# EEG_Inputs.net
KiCad netlist of a schematic drawn in Altium Designer
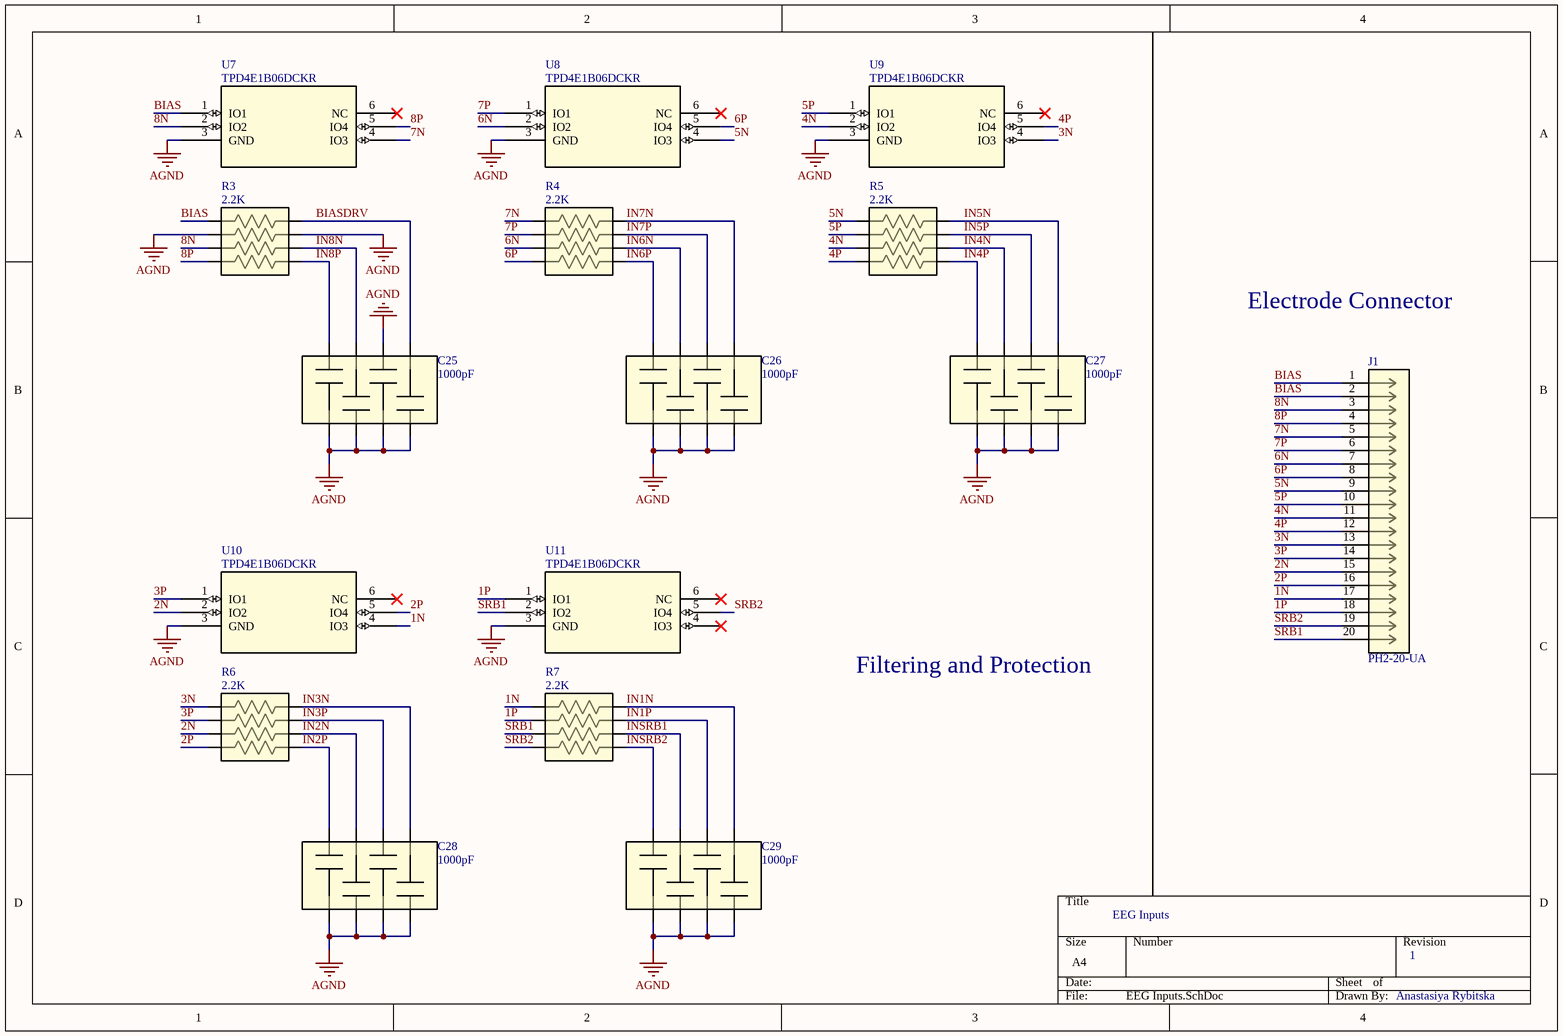
[diagram p0: EEG Inputs.SchDoc]

(export (version "E")
  (design (tool "Eeschema 10.0.6"))
  (components
    (comp (ref "C25")
      (value "CA0612KRX7R9BB102")
      (footprint "CAP_CA0612_3P2X1P6_YAG")
      (fields (field (name "CAPACITANCE") "1000pF"))
      (libsource (lib "Schlib1") (part "CA0612KRX7R9BB102"))
    )
    (comp (ref "C26")
      (value "CA0612KRX7R9BB102")
      (footprint "CAP_CA0612_3P2X1P6_YAG")
      (fields (field (name "CAPACITANCE") "1000pF"))
      (libsource (lib "Schlib1") (part "CA0612KRX7R9BB102"))
    )
    (comp (ref "C27")
      (value "CA0612KRX7R9BB102")
      (footprint "CAP_CA0612_3P2X1P6_YAG")
      (fields (field (name "CAPACITANCE") "1000pF"))
      (libsource (lib "Schlib1") (part "CA0612KRX7R9BB102"))
    )
    (comp (ref "C28")
      (value "CA0612KRX7R9BB102")
      (footprint "CAP_CA0612_3P2X1P6_YAG")
      (fields (field (name "CAPACITANCE") "1000pF"))
      (libsource (lib "Schlib1") (part "CA0612KRX7R9BB102"))
    )
    (comp (ref "C29")
      (value "CA0612KRX7R9BB102")
      (footprint "CAP_CA0612_3P2X1P6_YAG")
      (fields (field (name "CAPACITANCE") "1000pF"))
      (libsource (lib "Schlib1") (part "CA0612KRX7R9BB102"))
    )
    (comp (ref "J1")
      (value "PH2-20-UA")
      (footprint "CONN_PH2-20-UA_ADM")
      (description "No Description Available")
      (fields (field (name "COPYRIGHT") "Copyright (C) 2024 Ultra Librarian. All rights reserved."))
      (libsource (lib "Schlib1") (part "PH2-20-UA"))
    )
    (comp (ref "R3")
      (value "CAY16-2201F4LF")
      (footprint "CAY16_BRN")
      (description "No Description Available")
      (fields
        (field (name "RESISTANCE") "2.2K")
        (field (name "COPYRIGHT") "Copyright (C) 2023 Ultra Librarian. All rights reserved.")
      )
      (libsource (lib "Schlib1") (part "CAY16-2201F4LF"))
    )
    (comp (ref "R4")
      (value "CAY16-2201F4LF")
      (footprint "CAY16_BRN")
      (description "No Description Available")
      (fields
        (field (name "RESISTANCE") "2.2K")
        (field (name "COPYRIGHT") "Copyright (C) 2023 Ultra Librarian. All rights reserved.")
      )
      (libsource (lib "Schlib1") (part "CAY16-2201F4LF"))
    )
    (comp (ref "R5")
      (value "CAY16-2201F4LF")
      (footprint "CAY16_BRN")
      (description "No Description Available")
      (fields
        (field (name "RESISTANCE") "2.2K")
        (field (name "COPYRIGHT") "Copyright (C) 2023 Ultra Librarian. All rights reserved.")
      )
      (libsource (lib "Schlib1") (part "CAY16-2201F4LF"))
    )
    (comp (ref "R6")
      (value "CAY16-2201F4LF")
      (footprint "CAY16_BRN")
      (description "No Description Available")
      (fields
        (field (name "RESISTANCE") "2.2K")
        (field (name "COPYRIGHT") "Copyright (C) 2023 Ultra Librarian. All rights reserved.")
      )
      (libsource (lib "Schlib1") (part "CAY16-2201F4LF"))
    )
    (comp (ref "R7")
      (value "CAY16-2201F4LF")
      (footprint "CAY16_BRN")
      (description "No Description Available")
      (fields
        (field (name "RESISTANCE") "2.2K")
        (field (name "COPYRIGHT") "Copyright (C) 2023 Ultra Librarian. All rights reserved.")
      )
      (libsource (lib "Schlib1") (part "CAY16-2201F4LF"))
    )
    (comp (ref "U7")
      (value "TPD4E1B06DCKR")
      (footprint "DCK6_TEX")
      (description "No Description Available")
      (fields (field (name "COPYRIGHT") "Copyright (C) 2023 Ultra Librarian. All rights reserved."))
      (libsource (lib "Schlib1") (part "TPD4E1B06DCKR"))
    )
    (comp (ref "U8")
      (value "TPD4E1B06DCKR")
      (footprint "DCK6_TEX")
      (description "No Description Available")
      (fields (field (name "COPYRIGHT") "Copyright (C) 2023 Ultra Librarian. All rights reserved."))
      (libsource (lib "Schlib1") (part "TPD4E1B06DCKR"))
    )
    (comp (ref "U9")
      (value "TPD4E1B06DCKR")
      (footprint "DCK6_TEX")
      (description "No Description Available")
      (fields (field (name "COPYRIGHT") "Copyright (C) 2023 Ultra Librarian. All rights reserved."))
      (libsource (lib "Schlib1") (part "TPD4E1B06DCKR"))
    )
    (comp (ref "U10")
      (value "TPD4E1B06DCKR")
      (footprint "DCK6_TEX")
      (description "No Description Available")
      (fields (field (name "COPYRIGHT") "Copyright (C) 2023 Ultra Librarian. All rights reserved."))
      (libsource (lib "Schlib1") (part "TPD4E1B06DCKR"))
    )
    (comp (ref "U11")
      (value "TPD4E1B06DCKR")
      (footprint "DCK6_TEX")
      (description "No Description Available")
      (fields (field (name "COPYRIGHT") "Copyright (C) 2023 Ultra Librarian. All rights reserved."))
      (libsource (lib "Schlib1") (part "TPD4E1B06DCKR"))
    )
  )
  (nets
    (net (code "1") (name "/1N") (class "Default")
      (node (ref "J1") (pin "17") (pinfunction "17_17") (pintype "passive"))
      (node (ref "R7") (pin "1") (pinfunction "1_1") (pintype "passive"))
      (node (ref "U10") (pin "4") (pinfunction "IO3_4") (pintype "bidirectional"))
    )
    (net (code "2") (name "/1P") (class "Default")
      (node (ref "J1") (pin "18") (pinfunction "18_18") (pintype "passive"))
      (node (ref "R7") (pin "2") (pinfunction "2_2") (pintype "passive"))
      (node (ref "U11") (pin "1") (pinfunction "IO1_1") (pintype "bidirectional"))
    )
    (net (code "3") (name "/2N") (class "Default")
      (node (ref "J1") (pin "15") (pinfunction "15_15") (pintype "passive"))
      (node (ref "R6") (pin "3") (pinfunction "3_3") (pintype "passive"))
      (node (ref "U10") (pin "2") (pinfunction "IO2_2") (pintype "bidirectional"))
    )
    (net (code "4") (name "/2P") (class "Default")
      (node (ref "J1") (pin "16") (pinfunction "16_16") (pintype "passive"))
      (node (ref "R6") (pin "4") (pinfunction "4_4") (pintype "passive"))
      (node (ref "U10") (pin "5") (pinfunction "IO4_5") (pintype "bidirectional"))
    )
    (net (code "5") (name "/3N") (class "Default")
      (node (ref "J1") (pin "13") (pinfunction "13_13") (pintype "passive"))
      (node (ref "R6") (pin "1") (pinfunction "1_1") (pintype "passive"))
      (node (ref "U9") (pin "4") (pinfunction "IO3_4") (pintype "bidirectional"))
    )
    (net (code "6") (name "/3P") (class "Default")
      (node (ref "J1") (pin "14") (pinfunction "14_14") (pintype "passive"))
      (node (ref "R6") (pin "2") (pinfunction "2_2") (pintype "passive"))
      (node (ref "U10") (pin "1") (pinfunction "IO1_1") (pintype "bidirectional"))
    )
    (net (code "7") (name "/4N") (class "Default")
      (node (ref "J1") (pin "11") (pinfunction "11_11") (pintype "passive"))
      (node (ref "R5") (pin "3") (pinfunction "3_3") (pintype "passive"))
      (node (ref "U9") (pin "2") (pinfunction "IO2_2") (pintype "bidirectional"))
    )
    (net (code "8") (name "/4P") (class "Default")
      (node (ref "J1") (pin "12") (pinfunction "12_12") (pintype "passive"))
      (node (ref "R5") (pin "4") (pinfunction "4_4") (pintype "passive"))
      (node (ref "U9") (pin "5") (pinfunction "IO4_5") (pintype "bidirectional"))
    )
    (net (code "9") (name "/5N") (class "Default")
      (node (ref "J1") (pin "9") (pinfunction "9_9") (pintype "passive"))
      (node (ref "R5") (pin "1") (pinfunction "1_1") (pintype "passive"))
      (node (ref "U8") (pin "4") (pinfunction "IO3_4") (pintype "bidirectional"))
    )
    (net (code "10") (name "/5P") (class "Default")
      (node (ref "J1") (pin "10") (pinfunction "10_10") (pintype "passive"))
      (node (ref "R5") (pin "2") (pinfunction "2_2") (pintype "passive"))
      (node (ref "U9") (pin "1") (pinfunction "IO1_1") (pintype "bidirectional"))
    )
    (net (code "11") (name "/6N") (class "Default")
      (node (ref "J1") (pin "7") (pinfunction "7_7") (pintype "passive"))
      (node (ref "R4") (pin "3") (pinfunction "3_3") (pintype "passive"))
      (node (ref "U8") (pin "2") (pinfunction "IO2_2") (pintype "bidirectional"))
    )
    (net (code "12") (name "/6P") (class "Default")
      (node (ref "J1") (pin "8") (pinfunction "8_8") (pintype "passive"))
      (node (ref "R4") (pin "4") (pinfunction "4_4") (pintype "passive"))
      (node (ref "U8") (pin "5") (pinfunction "IO4_5") (pintype "bidirectional"))
    )
    (net (code "13") (name "/7N") (class "Default")
      (node (ref "J1") (pin "5") (pinfunction "5_5") (pintype "passive"))
      (node (ref "R4") (pin "1") (pinfunction "1_1") (pintype "passive"))
      (node (ref "U7") (pin "4") (pinfunction "IO3_4") (pintype "bidirectional"))
    )
    (net (code "14") (name "/7P") (class "Default")
      (node (ref "J1") (pin "6") (pinfunction "6_6") (pintype "passive"))
      (node (ref "R4") (pin "2") (pinfunction "2_2") (pintype "passive"))
      (node (ref "U8") (pin "1") (pinfunction "IO1_1") (pintype "bidirectional"))
    )
    (net (code "15") (name "/8N") (class "Default")
      (node (ref "J1") (pin "3") (pinfunction "3_3") (pintype "passive"))
      (node (ref "R3") (pin "3") (pinfunction "3_3") (pintype "passive"))
      (node (ref "U7") (pin "2") (pinfunction "IO2_2") (pintype "bidirectional"))
    )
    (net (code "16") (name "/8P") (class "Default")
      (node (ref "J1") (pin "4") (pinfunction "4_4") (pintype "passive"))
      (node (ref "R3") (pin "4") (pinfunction "4_4") (pintype "passive"))
      (node (ref "U7") (pin "5") (pinfunction "IO4_5") (pintype "bidirectional"))
    )
    (net (code "17") (name "/BIAS") (class "Default")
      (node (ref "J1") (pin "1") (pinfunction "1_1") (pintype "passive"))
      (node (ref "J1") (pin "2") (pinfunction "2_2") (pintype "passive"))
      (node (ref "R3") (pin "1") (pinfunction "1_1") (pintype "passive"))
      (node (ref "U7") (pin "1") (pinfunction "IO1_1") (pintype "bidirectional"))
    )
    (net (code "18") (name "/BIASDRV") (class "Default")
      (node (ref "C25") (pin "5") (pinfunction "5_5") (pintype "passive"))
      (node (ref "R3") (pin "8") (pinfunction "8_8") (pintype "passive"))
    )
    (net (code "19") (name "/IN1N") (class "Default")
      (node (ref "C29") (pin "5") (pinfunction "5_5") (pintype "passive"))
      (node (ref "R7") (pin "8") (pinfunction "8_8") (pintype "passive"))
    )
    (net (code "20") (name "/IN1P") (class "Default")
      (node (ref "C29") (pin "6") (pinfunction "6_6") (pintype "passive"))
      (node (ref "R7") (pin "7") (pinfunction "7_7") (pintype "passive"))
    )
    (net (code "21") (name "/IN2N") (class "Default")
      (node (ref "C28") (pin "7") (pinfunction "7_7") (pintype "passive"))
      (node (ref "R6") (pin "6") (pinfunction "6_6") (pintype "passive"))
    )
    (net (code "22") (name "/IN2P") (class "Default")
      (node (ref "C28") (pin "8") (pinfunction "8_8") (pintype "passive"))
      (node (ref "R6") (pin "5") (pinfunction "5_5") (pintype "passive"))
    )
    (net (code "23") (name "/IN3N") (class "Default")
      (node (ref "C28") (pin "5") (pinfunction "5_5") (pintype "passive"))
      (node (ref "R6") (pin "8") (pinfunction "8_8") (pintype "passive"))
    )
    (net (code "24") (name "/IN3P") (class "Default")
      (node (ref "C28") (pin "6") (pinfunction "6_6") (pintype "passive"))
      (node (ref "R6") (pin "7") (pinfunction "7_7") (pintype "passive"))
    )
    (net (code "25") (name "/IN4N") (class "Default")
      (node (ref "C27") (pin "7") (pinfunction "7_7") (pintype "passive"))
      (node (ref "R5") (pin "6") (pinfunction "6_6") (pintype "passive"))
    )
    (net (code "26") (name "/IN4P") (class "Default")
      (node (ref "C27") (pin "8") (pinfunction "8_8") (pintype "passive"))
      (node (ref "R5") (pin "5") (pinfunction "5_5") (pintype "passive"))
    )
    (net (code "27") (name "/IN5N") (class "Default")
      (node (ref "C27") (pin "5") (pinfunction "5_5") (pintype "passive"))
      (node (ref "R5") (pin "8") (pinfunction "8_8") (pintype "passive"))
    )
    (net (code "28") (name "/IN5P") (class "Default")
      (node (ref "C27") (pin "6") (pinfunction "6_6") (pintype "passive"))
      (node (ref "R5") (pin "7") (pinfunction "7_7") (pintype "passive"))
    )
    (net (code "29") (name "/IN6N") (class "Default")
      (node (ref "C26") (pin "7") (pinfunction "7_7") (pintype "passive"))
      (node (ref "R4") (pin "6") (pinfunction "6_6") (pintype "passive"))
    )
    (net (code "30") (name "/IN6P") (class "Default")
      (node (ref "C26") (pin "8") (pinfunction "8_8") (pintype "passive"))
      (node (ref "R4") (pin "5") (pinfunction "5_5") (pintype "passive"))
    )
    (net (code "31") (name "/IN7N") (class "Default")
      (node (ref "C26") (pin "5") (pinfunction "5_5") (pintype "passive"))
      (node (ref "R4") (pin "8") (pinfunction "8_8") (pintype "passive"))
    )
    (net (code "32") (name "/IN7P") (class "Default")
      (node (ref "C26") (pin "6") (pinfunction "6_6") (pintype "passive"))
      (node (ref "R4") (pin "7") (pinfunction "7_7") (pintype "passive"))
    )
    (net (code "33") (name "/IN8N") (class "Default")
      (node (ref "C25") (pin "7") (pinfunction "7_7") (pintype "passive"))
      (node (ref "R3") (pin "6") (pinfunction "6_6") (pintype "passive"))
    )
    (net (code "34") (name "/IN8P") (class "Default")
      (node (ref "C25") (pin "8") (pinfunction "8_8") (pintype "passive"))
      (node (ref "R3") (pin "5") (pinfunction "5_5") (pintype "passive"))
    )
    (net (code "35") (name "/INSRB1") (class "Default")
      (node (ref "C29") (pin "7") (pinfunction "7_7") (pintype "passive"))
      (node (ref "R7") (pin "6") (pinfunction "6_6") (pintype "passive"))
    )
    (net (code "36") (name "/INSRB2") (class "Default")
      (node (ref "C29") (pin "8") (pinfunction "8_8") (pintype "passive"))
      (node (ref "R7") (pin "5") (pinfunction "5_5") (pintype "passive"))
    )
    (net (code "37") (name "/SRB1") (class "Default")
      (node (ref "J1") (pin "20") (pinfunction "20_20") (pintype "passive"))
      (node (ref "R7") (pin "3") (pinfunction "3_3") (pintype "passive"))
      (node (ref "U11") (pin "2") (pinfunction "IO2_2") (pintype "bidirectional"))
    )
    (net (code "38") (name "/SRB2") (class "Default")
      (node (ref "J1") (pin "19") (pinfunction "19_19") (pintype "passive"))
      (node (ref "R7") (pin "4") (pinfunction "4_4") (pintype "passive"))
      (node (ref "U11") (pin "5") (pinfunction "IO4_5") (pintype "bidirectional"))
    )
    (net (code "39") (name "AGND") (class "Default")
      (node (ref "C25") (pin "1") (pinfunction "1_1") (pintype "passive"))
      (node (ref "C25") (pin "2") (pinfunction "2_2") (pintype "passive"))
      (node (ref "C25") (pin "3") (pinfunction "3_3") (pintype "passive"))
      (node (ref "C25") (pin "4") (pinfunction "4_4") (pintype "passive"))
      (node (ref "C25") (pin "6") (pinfunction "6_6") (pintype "passive"))
      (node (ref "C26") (pin "1") (pinfunction "1_1") (pintype "passive"))
      (node (ref "C26") (pin "2") (pinfunction "2_2") (pintype "passive"))
      (node (ref "C26") (pin "3") (pinfunction "3_3") (pintype "passive"))
      (node (ref "C26") (pin "4") (pinfunction "4_4") (pintype "passive"))
      (node (ref "C27") (pin "1") (pinfunction "1_1") (pintype "passive"))
      (node (ref "C27") (pin "2") (pinfunction "2_2") (pintype "passive"))
      (node (ref "C27") (pin "3") (pinfunction "3_3") (pintype "passive"))
      (node (ref "C27") (pin "4") (pinfunction "4_4") (pintype "passive"))
      (node (ref "C28") (pin "1") (pinfunction "1_1") (pintype "passive"))
      (node (ref "C28") (pin "2") (pinfunction "2_2") (pintype "passive"))
      (node (ref "C28") (pin "3") (pinfunction "3_3") (pintype "passive"))
      (node (ref "C28") (pin "4") (pinfunction "4_4") (pintype "passive"))
      (node (ref "C29") (pin "1") (pinfunction "1_1") (pintype "passive"))
      (node (ref "C29") (pin "2") (pinfunction "2_2") (pintype "passive"))
      (node (ref "C29") (pin "3") (pinfunction "3_3") (pintype "passive"))
      (node (ref "C29") (pin "4") (pinfunction "4_4") (pintype "passive"))
      (node (ref "R3") (pin "2") (pinfunction "2_2") (pintype "passive"))
      (node (ref "R3") (pin "7") (pinfunction "7_7") (pintype "passive"))
      (node (ref "U10") (pin "3") (pinfunction "GND_3") (pintype "power_in"))
      (node (ref "U11") (pin "3") (pinfunction "GND_3") (pintype "power_in"))
      (node (ref "U7") (pin "3") (pinfunction "GND_3") (pintype "power_in"))
      (node (ref "U8") (pin "3") (pinfunction "GND_3") (pintype "power_in"))
      (node (ref "U9") (pin "3") (pinfunction "GND_3") (pintype "power_in"))
    )
    (net (code "40") (name "unconnected-(U7-NC-Pad6)") (class "Default")
      (node (ref "U7") (pin "6") (pinfunction "NC_6") (pintype "passive+no_connect"))
    )
    (net (code "41") (name "unconnected-(U8-NC-Pad6)") (class "Default")
      (node (ref "U8") (pin "6") (pinfunction "NC_6") (pintype "passive+no_connect"))
    )
    (net (code "42") (name "unconnected-(U9-NC-Pad6)") (class "Default")
      (node (ref "U9") (pin "6") (pinfunction "NC_6") (pintype "passive+no_connect"))
    )
    (net (code "43") (name "unconnected-(U10-NC-Pad6)") (class "Default")
      (node (ref "U10") (pin "6") (pinfunction "NC_6") (pintype "passive+no_connect"))
    )
    (net (code "44") (name "unconnected-(U11-IO3-Pad4)") (class "Default")
      (node (ref "U11") (pin "4") (pinfunction "IO3_4") (pintype "bidirectional+no_connect"))
    )
    (net (code "45") (name "unconnected-(U11-NC-Pad6)") (class "Default")
      (node (ref "U11") (pin "6") (pinfunction "NC_6") (pintype "passive+no_connect"))
    )
  )
)
